# schematic_1.net
KiCad netlist of a schematic drawn in EAGLE
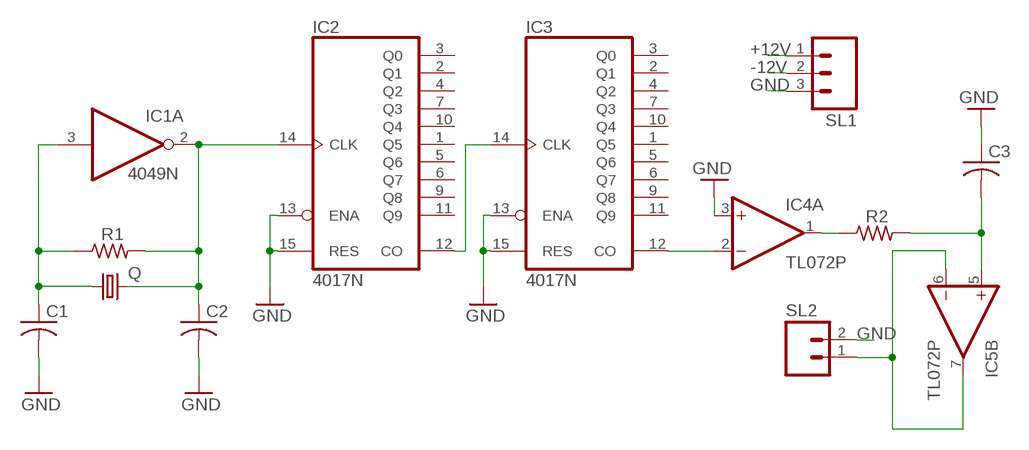
[diagram p0: schematic, sheet 1]

(export (version "E")
  (design (tool "Eeschema 10.0.6"))
  (components
    (comp (ref "C1")
      (value "C-US025-024X044")
      (footprint "eagle-import:C025-024X044")
      (libsource (lib "eagle-import") (part "C-US025-024X044"))
    )
    (comp (ref "C2")
      (value "C-US025-024X044")
      (footprint "eagle-import:C025-024X044")
      (libsource (lib "eagle-import") (part "C-US025-024X044"))
    )
    (comp (ref "C3")
      (value "C-US025-024X044")
      (footprint "eagle-import:C025-024X044")
      (libsource (lib "eagle-import") (part "C-US025-024X044"))
    )
    (comp (ref "IC1")
      (value "4049N")
      (footprint "eagle-import:DIL16")
      (libsource (lib "eagle-import") (part "4049N"))
    )
    (comp (ref "IC2")
      (value "4017N")
      (footprint "eagle-import:DIL16")
      (libsource (lib "eagle-import") (part "4017N"))
    )
    (comp (ref "IC3")
      (value "4017N")
      (footprint "eagle-import:DIL16")
      (libsource (lib "eagle-import") (part "4017N"))
    )
    (comp (ref "IC4")
      (value "TL072P")
      (footprint "eagle-import:DIL08")
      (libsource (lib "eagle-import") (part "TL072P"))
    )
    (comp (ref "IC5")
      (value "TL072P")
      (footprint "eagle-import:DIL08")
      (libsource (lib "eagle-import") (part "TL072P"))
    )
    (comp (ref "Q")
      (value "CRYSTALHC49S")
      (footprint "eagle-import:HC49_S")
      (libsource (lib "eagle-import") (part "CRYSTALHC49S"))
    )
    (comp (ref "R1")
      (value "R-US_0204/7")
      (footprint "eagle-import:0204_7")
      (libsource (lib "eagle-import") (part "R-US_0204/7"))
    )
    (comp (ref "R2")
      (value "R-US_0204/7")
      (footprint "eagle-import:0204_7")
      (libsource (lib "eagle-import") (part "R-US_0204/7"))
    )
    (comp (ref "SL1")
      (value "M03")
      (footprint "eagle-import:03P")
      (libsource (lib "eagle-import") (part "M03"))
    )
    (comp (ref "SL2")
      (value "M02")
      (footprint "eagle-import:02P")
      (libsource (lib "eagle-import") (part "M02"))
    )
  )
  (nets
    (net (code "1") (name "/+12V") (class "Default")
      (node (ref "SL1") (pin "1") (pinfunction "1_1") (pintype "passive"))
    )
    (net (code "2") (name "/-12V") (class "Default")
      (node (ref "SL1") (pin "2") (pinfunction "2_2") (pintype "passive"))
    )
    (net (code "3") (name "GND") (class "Default")
      (node (ref "C1") (pin "2") (pinfunction "2_2") (pintype "passive"))
      (node (ref "C2") (pin "2") (pinfunction "2_2") (pintype "passive"))
      (node (ref "C3") (pin "1") (pinfunction "1_1") (pintype "passive"))
      (node (ref "IC2") (pin "13") (pinfunction "ENA_13") (pintype "input"))
      (node (ref "IC2") (pin "15") (pinfunction "RES_15") (pintype "input"))
      (node (ref "IC3") (pin "13") (pinfunction "ENA_13") (pintype "input"))
      (node (ref "IC3") (pin "15") (pinfunction "RES_15") (pintype "input"))
      (node (ref "IC4") (pin "3") (pinfunction "+IN_3") (pintype "input"))
      (node (ref "SL1") (pin "3") (pinfunction "3_3") (pintype "passive"))
      (node (ref "SL2") (pin "2") (pinfunction "2_2") (pintype "passive"))
    )
    (net (code "4") (name "Net-(IC1A-I)") (class "Default")
      (node (ref "C1") (pin "1") (pinfunction "1_1") (pintype "passive"))
      (node (ref "IC1") (pin "3") (pinfunction "I_3") (pintype "input"))
      (node (ref "Q") (pin "1") (pinfunction "1_1") (pintype "passive"))
      (node (ref "R1") (pin "1") (pinfunction "1_1") (pintype "passive"))
    )
    (net (code "5") (name "Net-(IC1A-O)") (class "Default")
      (node (ref "C2") (pin "1") (pinfunction "1_1") (pintype "passive"))
      (node (ref "IC1") (pin "2") (pinfunction "O_2") (pintype "output"))
      (node (ref "IC2") (pin "14") (pinfunction "CLK_14") (pintype "input"))
      (node (ref "Q") (pin "2") (pinfunction "2_2") (pintype "passive"))
      (node (ref "R1") (pin "2") (pinfunction "2_2") (pintype "passive"))
    )
    (net (code "6") (name "Net-(IC2A-CO)") (class "Default")
      (node (ref "IC2") (pin "12") (pinfunction "CO_12") (pintype "output"))
      (node (ref "IC3") (pin "14") (pinfunction "CLK_14") (pintype "input"))
    )
    (net (code "7") (name "Net-(IC3A-CO)") (class "Default")
      (node (ref "IC3") (pin "12") (pinfunction "CO_12") (pintype "output"))
      (node (ref "IC4") (pin "2") (pinfunction "-IN_2") (pintype "input"))
    )
    (net (code "8") (name "Net-(IC4A-OUT)") (class "Default")
      (node (ref "IC4") (pin "1") (pinfunction "OUT_1") (pintype "output"))
      (node (ref "R2") (pin "1") (pinfunction "1_1") (pintype "passive"))
    )
    (net (code "9") (name "Net-(IC5B-+IN)") (class "Default")
      (node (ref "C3") (pin "2") (pinfunction "2_2") (pintype "passive"))
      (node (ref "IC5") (pin "5") (pinfunction "+IN_5") (pintype "input"))
      (node (ref "R2") (pin "2") (pinfunction "2_2") (pintype "passive"))
    )
    (net (code "10") (name "Net-(IC5B--IN)") (class "Default")
      (node (ref "IC5") (pin "6") (pinfunction "-IN_6") (pintype "input"))
      (node (ref "IC5") (pin "7") (pinfunction "OUT_7") (pintype "output"))
      (node (ref "SL2") (pin "1") (pinfunction "1_1") (pintype "passive"))
    )
    (net (code "11") (name "unconnected-(IC2A-Q0-Pad3)") (class "Default")
      (node (ref "IC2") (pin "3") (pinfunction "Q0_3") (pintype "output"))
    )
    (net (code "12") (name "unconnected-(IC2A-Q1-Pad2)") (class "Default")
      (node (ref "IC2") (pin "2") (pinfunction "Q1_2") (pintype "output"))
    )
    (net (code "13") (name "unconnected-(IC2A-Q2-Pad4)") (class "Default")
      (node (ref "IC2") (pin "4") (pinfunction "Q2_4") (pintype "output"))
    )
    (net (code "14") (name "unconnected-(IC2A-Q3-Pad7)") (class "Default")
      (node (ref "IC2") (pin "7") (pinfunction "Q3_7") (pintype "output"))
    )
    (net (code "15") (name "unconnected-(IC2A-Q4-Pad10)") (class "Default")
      (node (ref "IC2") (pin "10") (pinfunction "Q4_10") (pintype "output"))
    )
    (net (code "16") (name "unconnected-(IC2A-Q5-Pad1)") (class "Default")
      (node (ref "IC2") (pin "1") (pinfunction "Q5_1") (pintype "output"))
    )
    (net (code "17") (name "unconnected-(IC2A-Q6-Pad5)") (class "Default")
      (node (ref "IC2") (pin "5") (pinfunction "Q6_5") (pintype "output"))
    )
    (net (code "18") (name "unconnected-(IC2A-Q7-Pad6)") (class "Default")
      (node (ref "IC2") (pin "6") (pinfunction "Q7_6") (pintype "output"))
    )
    (net (code "19") (name "unconnected-(IC2A-Q8-Pad9)") (class "Default")
      (node (ref "IC2") (pin "9") (pinfunction "Q8_9") (pintype "output"))
    )
    (net (code "20") (name "unconnected-(IC2A-Q9-Pad11)") (class "Default")
      (node (ref "IC2") (pin "11") (pinfunction "Q9_11") (pintype "output"))
    )
    (net (code "21") (name "unconnected-(IC3A-Q0-Pad3)") (class "Default")
      (node (ref "IC3") (pin "3") (pinfunction "Q0_3") (pintype "output"))
    )
    (net (code "22") (name "unconnected-(IC3A-Q1-Pad2)") (class "Default")
      (node (ref "IC3") (pin "2") (pinfunction "Q1_2") (pintype "output"))
    )
    (net (code "23") (name "unconnected-(IC3A-Q2-Pad4)") (class "Default")
      (node (ref "IC3") (pin "4") (pinfunction "Q2_4") (pintype "output"))
    )
    (net (code "24") (name "unconnected-(IC3A-Q3-Pad7)") (class "Default")
      (node (ref "IC3") (pin "7") (pinfunction "Q3_7") (pintype "output"))
    )
    (net (code "25") (name "unconnected-(IC3A-Q4-Pad10)") (class "Default")
      (node (ref "IC3") (pin "10") (pinfunction "Q4_10") (pintype "output"))
    )
    (net (code "26") (name "unconnected-(IC3A-Q5-Pad1)") (class "Default")
      (node (ref "IC3") (pin "1") (pinfunction "Q5_1") (pintype "output"))
    )
    (net (code "27") (name "unconnected-(IC3A-Q6-Pad5)") (class "Default")
      (node (ref "IC3") (pin "5") (pinfunction "Q6_5") (pintype "output"))
    )
    (net (code "28") (name "unconnected-(IC3A-Q7-Pad6)") (class "Default")
      (node (ref "IC3") (pin "6") (pinfunction "Q7_6") (pintype "output"))
    )
    (net (code "29") (name "unconnected-(IC3A-Q8-Pad9)") (class "Default")
      (node (ref "IC3") (pin "9") (pinfunction "Q8_9") (pintype "output"))
    )
    (net (code "30") (name "unconnected-(IC3A-Q9-Pad11)") (class "Default")
      (node (ref "IC3") (pin "11") (pinfunction "Q9_11") (pintype "output"))
    )
  )
)
